# Presencia_Agua.net
KiCad netlist of a schematic drawn in Altium Designer
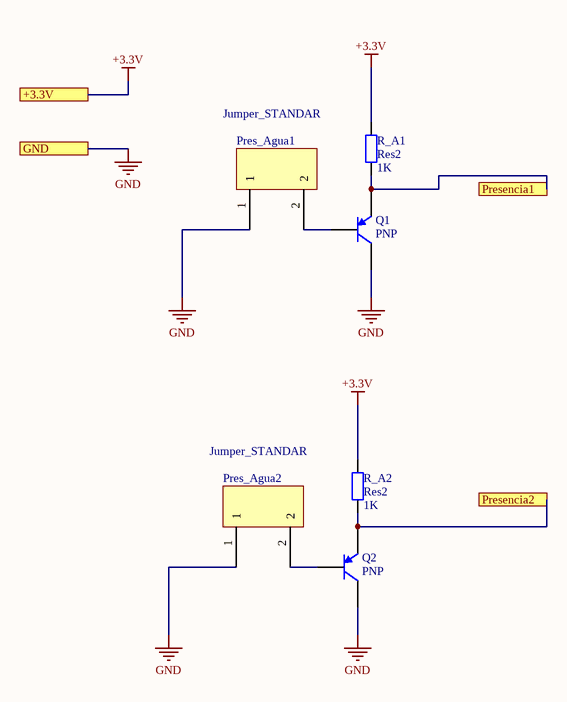
[diagram p0: Presencia_Agua.SchDoc]

(export (version "E")
  (design (tool "Eeschema 10.0.6"))
  (components
    (comp (ref "Pres_Agua1")
      (value "Jumper_STANDAR")
      (footprint "HDR1X2H")
      (libsource (lib "XSUB_COMP") (part "Jumper_STANDAR"))
    )
    (comp (ref "Pres_Agua2")
      (value "Jumper_STANDAR")
      (footprint "HDR1X2H")
      (libsource (lib "XSUB_COMP") (part "Jumper_STANDAR"))
    )
    (comp (ref "Q1")
      (value "PNP")
      (footprint "SOT-23B_N")
      (description "PNP Bipolar Transistor")
      (fields (field (name "PUBLISHER") "Altium Limited"))
      (libsource (lib "Miscellaneous Devices") (part "PNP"))
    )
    (comp (ref "Q2")
      (value "PNP")
      (footprint "SOT-23B_N")
      (description "PNP Bipolar Transistor")
      (fields (field (name "PUBLISHER") "Altium Limited"))
      (libsource (lib "Miscellaneous Devices") (part "PNP"))
    )
    (comp (ref "R_A1")
      (value "Res2")
      (footprint "AXIAL-0.4")
      (description "Resistor")
      (fields (field (name "ALTIUM_VALUE") "1K") (field (name "PUBLISHER") "Altium Limited"))
      (libsource (lib "Miscellaneous Devices") (part "Res2"))
    )
    (comp (ref "R_A2")
      (value "Res2")
      (footprint "AXIAL-0.4")
      (description "Resistor")
      (fields (field (name "ALTIUM_VALUE") "1K") (field (name "PUBLISHER") "Altium Limited"))
      (libsource (lib "Miscellaneous Devices") (part "Res2"))
    )
  )
  (nets
    (net (code "1") (name "+3.3V") (class "Default")
      (node (ref "R_A1") (pin "2") (pinfunction "2_2") (pintype "passive"))
      (node (ref "R_A2") (pin "2") (pinfunction "2_2") (pintype "passive"))
    )
    (net (code "2") (name "/Presencia1") (class "Default")
      (node (ref "Q1") (pin "3") (pinfunction "E_3") (pintype "passive"))
      (node (ref "R_A1") (pin "1") (pinfunction "1_1") (pintype "passive"))
    )
    (net (code "3") (name "/Presencia2") (class "Default")
      (node (ref "Q2") (pin "3") (pinfunction "E_3") (pintype "passive"))
      (node (ref "R_A2") (pin "1") (pinfunction "1_1") (pintype "passive"))
    )
    (net (code "4") (name "GND") (class "Default")
      (node (ref "Pres_Agua1") (pin "1") (pinfunction "1_1") (pintype "passive"))
      (node (ref "Pres_Agua2") (pin "1") (pinfunction "1_1") (pintype "passive"))
      (node (ref "Q1") (pin "1") (pinfunction "C_1") (pintype "passive"))
      (node (ref "Q2") (pin "1") (pinfunction "C_1") (pintype "passive"))
    )
    (net (code "5") (name "Net-(Q1-B)") (class "Default")
      (node (ref "Pres_Agua1") (pin "2") (pinfunction "2_2") (pintype "passive"))
      (node (ref "Q1") (pin "2") (pinfunction "B_2") (pintype "passive"))
    )
    (net (code "6") (name "Net-(Q2-B)") (class "Default")
      (node (ref "Pres_Agua2") (pin "2") (pinfunction "2_2") (pintype "passive"))
      (node (ref "Q2") (pin "2") (pinfunction "B_2") (pintype "passive"))
    )
  )
)
